# Arse_LFR.net
KiCad netlist of a schematic drawn in EasyEDA
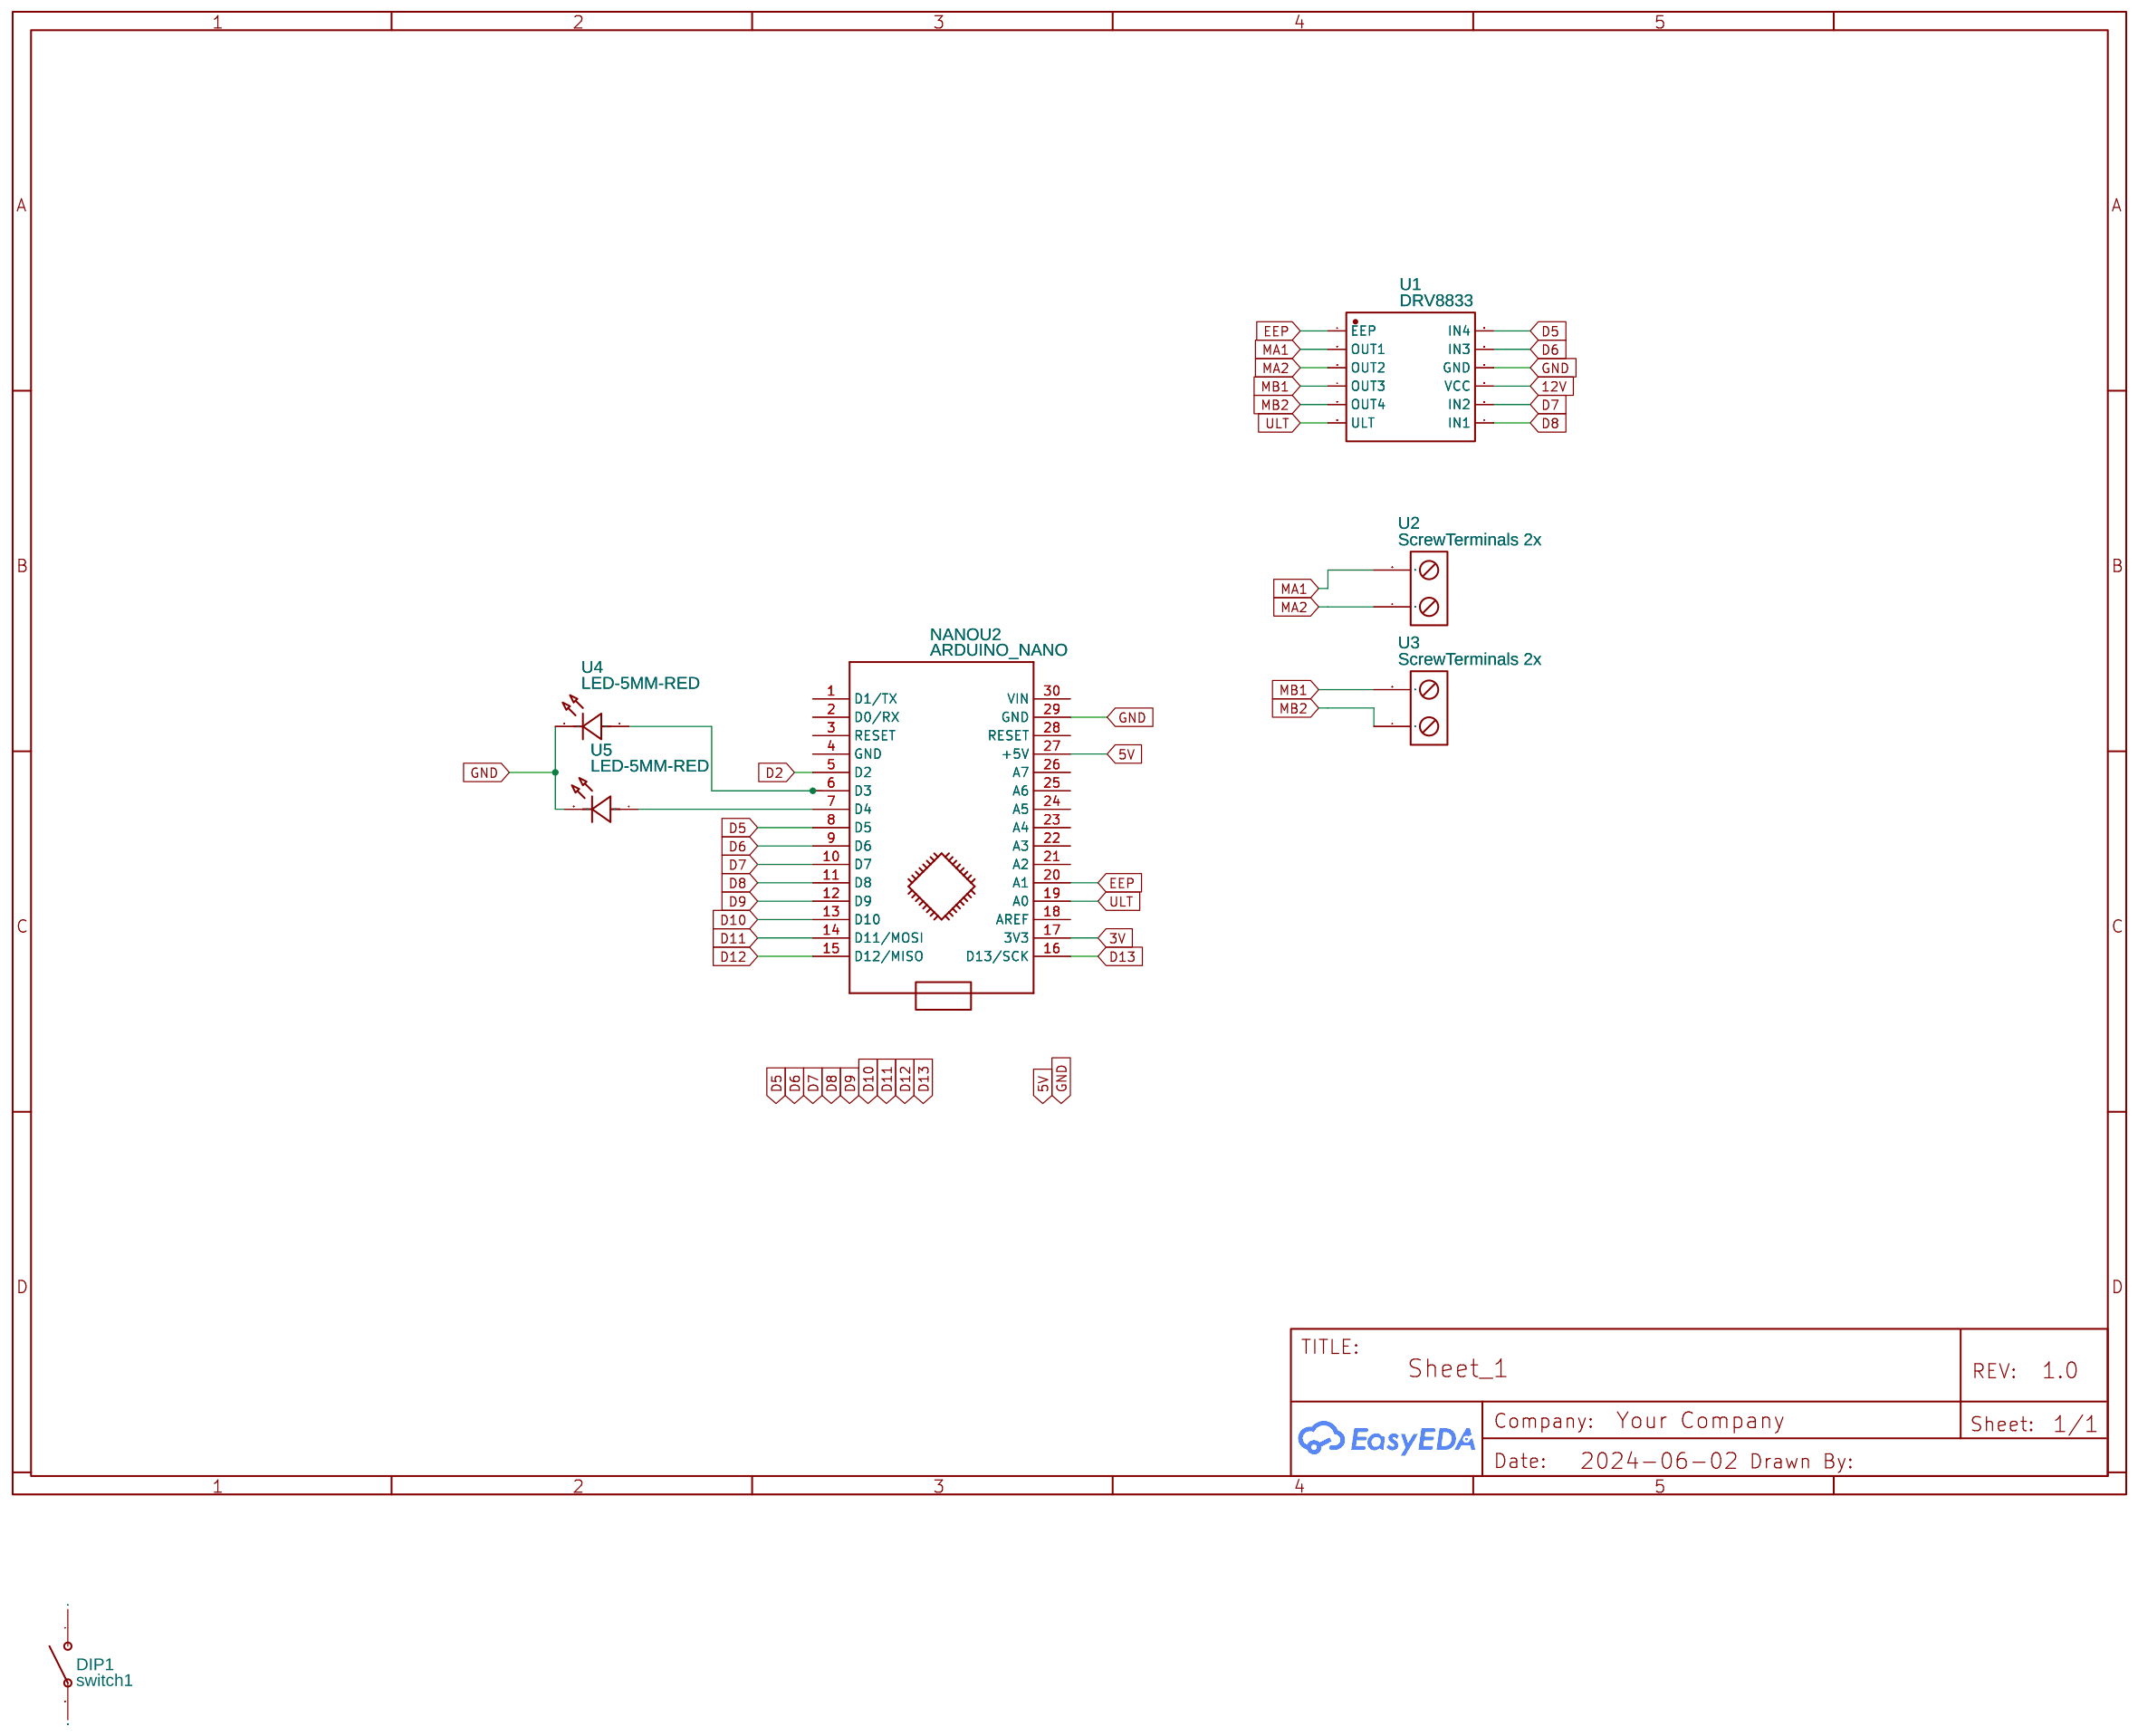
[diagram p0: schematic sheet]

(export (version "E")
  (design (tool "Eeschema 10.0.6"))
  (components
    (comp (ref "DIP1")
      (value "switch1")
      (fields (field (name "Manufacturer Part") "DIP switchEI-08") (field (name "Manufacturer") "DIP"))
      (libsource (lib "") (part "switch1"))
    )
    (comp (ref "NANOU2")
      (value "ARDUINO_NANO")
      (fields (field (name "Manufacturer Part") "?"))
      (libsource (lib "") (part "Unknown_555_-395"))
    )
    (comp (ref "U1") (value "DRV8833") (libsource (lib "") (part "DRV8833")))
    (comp (ref "U2") (value "ScrewTerminals 2x") (libsource (lib "") (part "ScrewTerminals 2x")))
    (comp (ref "U3") (value "ScrewTerminals 2x") (libsource (lib "") (part "ScrewTerminals 2x")))
    (comp (ref "U4")
      (value "LED-5MM-RED")
      (fields (field (name "Manufacturer Part") "SFH 313 FA") (field (name "Manufacturer") "OSRAM(欧司朗)"))
      (libsource (lib "") (part "LED-5MM-RED"))
    )
    (comp (ref "U5")
      (value "LED-5MM-RED")
      (fields (field (name "Manufacturer Part") "SFH 313 FA") (field (name "Manufacturer") "OSRAM(欧司朗)"))
      (libsource (lib "") (part "LED-5MM-RED"))
    )
  )
  (nets
    (net (code "1") (name "3V") (class "Default")
      (node (ref "NANOU2") (pin "17") (pinfunction "3V3_17") (pintype "unspecified"))
    )
    (net (code "2") (name "5V") (class "Default")
      (node (ref "NANOU2") (pin "27") (pinfunction "+5V_27") (pintype "unspecified"))
    )
    (net (code "3") (name "12V") (class "Default")
      (node (ref "U1") (pin "9") (pinfunction "VCC_9") (pintype "unspecified"))
    )
    (net (code "4") (name "D2") (class "Default")
      (node (ref "NANOU2") (pin "5") (pinfunction "D2_5") (pintype "unspecified"))
    )
    (net (code "5") (name "D5") (class "Default")
      (node (ref "NANOU2") (pin "8") (pinfunction "D5_8") (pintype "unspecified"))
      (node (ref "U1") (pin "12") (pinfunction "IN4_12") (pintype "unspecified"))
    )
    (net (code "6") (name "D6") (class "Default")
      (node (ref "NANOU2") (pin "9") (pinfunction "D6_9") (pintype "unspecified"))
      (node (ref "U1") (pin "11") (pinfunction "IN3_11") (pintype "unspecified"))
    )
    (net (code "7") (name "D7") (class "Default")
      (node (ref "NANOU2") (pin "10") (pinfunction "D7_10") (pintype "unspecified"))
      (node (ref "U1") (pin "8") (pinfunction "IN2_8") (pintype "unspecified"))
    )
    (net (code "8") (name "D8") (class "Default")
      (node (ref "NANOU2") (pin "11") (pinfunction "D8_11") (pintype "unspecified"))
      (node (ref "U1") (pin "7") (pinfunction "IN1_7") (pintype "unspecified"))
    )
    (net (code "9") (name "D9") (class "Default")
      (node (ref "NANOU2") (pin "12") (pinfunction "D9_12") (pintype "unspecified"))
    )
    (net (code "10") (name "D10") (class "Default")
      (node (ref "NANOU2") (pin "13") (pinfunction "D10_13") (pintype "unspecified"))
    )
    (net (code "11") (name "D11") (class "Default")
      (node (ref "NANOU2") (pin "14") (pinfunction "D11/MOSI_14") (pintype "unspecified"))
    )
    (net (code "12") (name "D12") (class "Default")
      (node (ref "NANOU2") (pin "15") (pinfunction "D12/MISO_15") (pintype "unspecified"))
    )
    (net (code "13") (name "D13") (class "Default")
      (node (ref "NANOU2") (pin "16") (pinfunction "D13/SCK_16") (pintype "unspecified"))
    )
    (net (code "14") (name "EEP") (class "Default")
      (node (ref "NANOU2") (pin "20") (pinfunction "A1_20") (pintype "unspecified"))
      (node (ref "U1") (pin "1") (pinfunction "EEP_1") (pintype "unspecified"))
    )
    (net (code "15") (name "GND") (class "Default")
      (node (ref "NANOU2") (pin "29") (pinfunction "GND_29") (pintype "unspecified"))
      (node (ref "U1") (pin "10") (pinfunction "GND_10") (pintype "unspecified"))
      (node (ref "U4") (pin "2") (pinfunction "K_2") (pintype "unspecified"))
      (node (ref "U5") (pin "2") (pinfunction "K_2") (pintype "unspecified"))
    )
    (net (code "16") (name "MA1") (class "Default")
      (node (ref "U1") (pin "2") (pinfunction "OUT1_2") (pintype "unspecified"))
      (node (ref "U2") (pin "2") (pinfunction "2_2") (pintype "unspecified"))
    )
    (net (code "17") (name "MA2") (class "Default")
      (node (ref "U1") (pin "3") (pinfunction "OUT2_3") (pintype "unspecified"))
      (node (ref "U2") (pin "1") (pinfunction "1_1") (pintype "unspecified"))
    )
    (net (code "18") (name "MB1") (class "Default")
      (node (ref "U1") (pin "4") (pinfunction "OUT3_4") (pintype "unspecified"))
      (node (ref "U3") (pin "2") (pinfunction "2_2") (pintype "unspecified"))
    )
    (net (code "19") (name "MB2") (class "Default")
      (node (ref "U1") (pin "5") (pinfunction "OUT4_5") (pintype "unspecified"))
      (node (ref "U3") (pin "1") (pinfunction "1_1") (pintype "unspecified"))
    )
    (net (code "20") (name "Net-(NANOU2-D3)") (class "Default")
      (node (ref "NANOU2") (pin "6") (pinfunction "D3_6") (pintype "unspecified"))
      (node (ref "U4") (pin "1") (pinfunction "A_1") (pintype "unspecified"))
    )
    (net (code "21") (name "Net-(NANOU2-D4)") (class "Default")
      (node (ref "NANOU2") (pin "7") (pinfunction "D4_7") (pintype "unspecified"))
      (node (ref "U5") (pin "1") (pinfunction "A_1") (pintype "unspecified"))
    )
    (net (code "22") (name "ULT") (class "Default")
      (node (ref "NANOU2") (pin "19") (pinfunction "A0_19") (pintype "unspecified"))
      (node (ref "U1") (pin "6") (pinfunction "ULT_6") (pintype "unspecified"))
    )
    (net (code "23") (name "unconnected-(DIP1-Pad1)") (class "Default")
      (node (ref "DIP1") (pin "1") (pinfunction "1_1") (pintype "unspecified"))
    )
    (net (code "24") (name "unconnected-(DIP1-Pad2)") (class "Default")
      (node (ref "DIP1") (pin "2") (pinfunction "2_2") (pintype "unspecified"))
    )
    (net (code "25") (name "unconnected-(NANOU2-A2-Pad21)") (class "Default")
      (node (ref "NANOU2") (pin "21") (pinfunction "A2_21") (pintype "unspecified"))
    )
    (net (code "26") (name "unconnected-(NANOU2-A3-Pad22)") (class "Default")
      (node (ref "NANOU2") (pin "22") (pinfunction "A3_22") (pintype "unspecified"))
    )
    (net (code "27") (name "unconnected-(NANOU2-A4-Pad23)") (class "Default")
      (node (ref "NANOU2") (pin "23") (pinfunction "A4_23") (pintype "unspecified"))
    )
    (net (code "28") (name "unconnected-(NANOU2-A5-Pad24)") (class "Default")
      (node (ref "NANOU2") (pin "24") (pinfunction "A5_24") (pintype "unspecified"))
    )
    (net (code "29") (name "unconnected-(NANOU2-A6-Pad25)") (class "Default")
      (node (ref "NANOU2") (pin "25") (pinfunction "A6_25") (pintype "unspecified"))
    )
    (net (code "30") (name "unconnected-(NANOU2-A7-Pad26)") (class "Default")
      (node (ref "NANOU2") (pin "26") (pinfunction "A7_26") (pintype "unspecified"))
    )
    (net (code "31") (name "unconnected-(NANOU2-AREF-Pad18)") (class "Default")
      (node (ref "NANOU2") (pin "18") (pinfunction "AREF_18") (pintype "unspecified"))
    )
    (net (code "32") (name "unconnected-(NANOU2-D0{slash}RX-Pad2)") (class "Default")
      (node (ref "NANOU2") (pin "2") (pinfunction "D0/RX_2") (pintype "unspecified"))
    )
    (net (code "33") (name "unconnected-(NANOU2-D1{slash}TX-Pad1)") (class "Default")
      (node (ref "NANOU2") (pin "1") (pinfunction "D1/TX_1") (pintype "unspecified"))
    )
    (net (code "34") (name "unconnected-(NANOU2-GND-Pad4)") (class "Default")
      (node (ref "NANOU2") (pin "4") (pinfunction "GND_4") (pintype "unspecified"))
    )
    (net (code "35") (name "unconnected-(NANOU2-RESET-Pad3)") (class "Default")
      (node (ref "NANOU2") (pin "3") (pinfunction "RESET_3") (pintype "unspecified"))
    )
    (net (code "36") (name "unconnected-(NANOU2-RESET-Pad28)") (class "Default")
      (node (ref "NANOU2") (pin "28") (pinfunction "RESET_28") (pintype "unspecified"))
    )
    (net (code "37") (name "unconnected-(NANOU2-VIN-Pad30)") (class "Default")
      (node (ref "NANOU2") (pin "30") (pinfunction "VIN_30") (pintype "unspecified"))
    )
  )
)
